# PMI_MotorDriver.net
KiCad netlist of a schematic drawn in Altium Designer
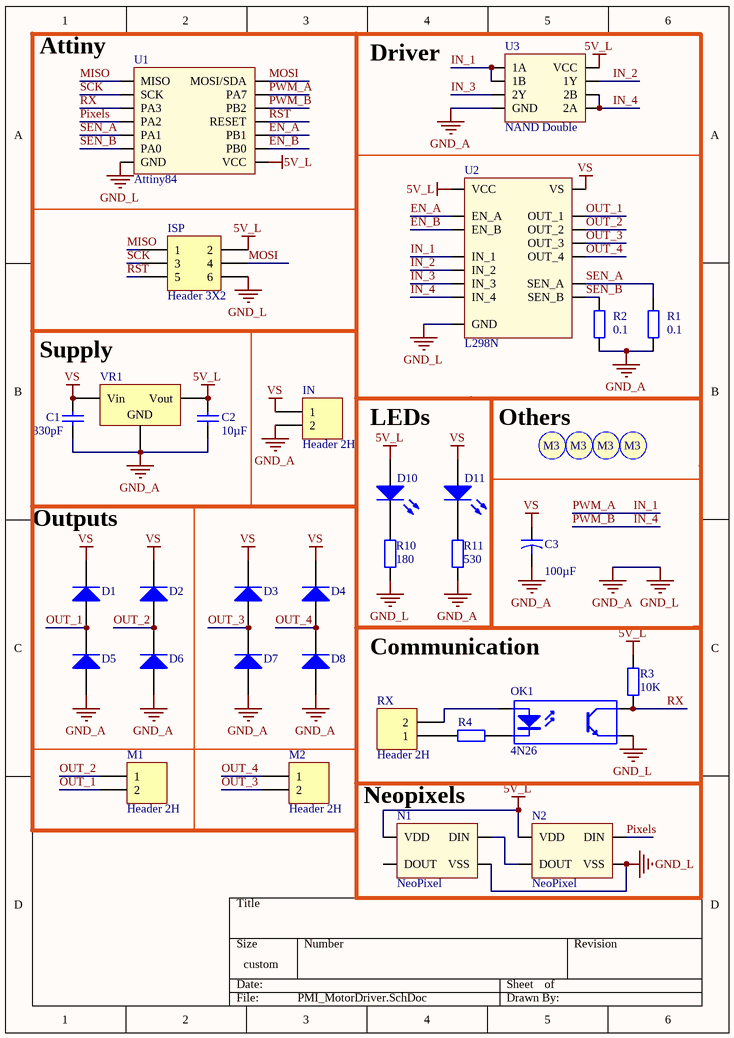
[diagram p0: PMI_MotorDriver.SchDoc]

(export (version "E")
  (design (tool "Eeschema 10.0.6"))
  (components
    (comp (ref "C1")
      (value "330pF")
      (footprint "3.2X1.6X1.1")
      (description "Capacitor")
      (fields (field (name "Comment") "Cap") (field (name "PUBLISHER") "Altium Limited"))
      (libsource (lib "Miscellaneous Devices") (part "Cap"))
    )
    (comp (ref "C2")
      (value "10µF")
      (footprint "3.2X1.6X1.1")
      (description "Capacitor")
      (fields (field (name "Comment") "Cap") (field (name "PUBLISHER") "Altium Limited"))
      (libsource (lib "Miscellaneous Devices") (part "Cap"))
    )
    (comp (ref "C3")
      (value "100µF")
      (footprint "Condensateur")
      (description "Capacitor")
      (fields (field (name "Comment") "Cap2") (field (name "PUBLISHER") "Altium Limited"))
      (libsource (lib "Miscellaneous Devices") (part "Cap2"))
    )
    (comp (ref "D1")
      (value "GF1G-E3/5CA (710-2976)")
      (footprint "DO-214BA")
      (description "Default Diode")
      (fields (field (name "PUBLISHER") "Altium Limited"))
      (libsource (lib "Miscellaneous Devices") (part "Diode"))
    )
    (comp (ref "D2")
      (value "Diode")
      (footprint "DO-214BA")
      (description "Default Diode")
      (fields (field (name "PUBLISHER") "Altium Limited"))
      (libsource (lib "Miscellaneous Devices") (part "Diode"))
    )
    (comp (ref "D3")
      (value "Diode")
      (footprint "DO-214BA")
      (description "Default Diode")
      (fields (field (name "PUBLISHER") "Altium Limited"))
      (libsource (lib "Miscellaneous Devices") (part "Diode"))
    )
    (comp (ref "D4")
      (value "Diode")
      (footprint "DO-214BA")
      (description "Default Diode")
      (fields (field (name "PUBLISHER") "Altium Limited"))
      (libsource (lib "Miscellaneous Devices") (part "Diode"))
    )
    (comp (ref "D5")
      (value "Diode")
      (footprint "DO-214BA")
      (description "Default Diode")
      (fields (field (name "PUBLISHER") "Altium Limited"))
      (libsource (lib "Miscellaneous Devices") (part "Diode"))
    )
    (comp (ref "D6")
      (value "Diode")
      (footprint "DO-214BA")
      (description "Default Diode")
      (fields (field (name "PUBLISHER") "Altium Limited"))
      (libsource (lib "Miscellaneous Devices") (part "Diode"))
    )
    (comp (ref "D7")
      (value "Diode")
      (footprint "DO-214BA")
      (description "Default Diode")
      (fields (field (name "PUBLISHER") "Altium Limited"))
      (libsource (lib "Miscellaneous Devices") (part "Diode"))
    )
    (comp (ref "D8")
      (value "Diode")
      (footprint "DO-214BA")
      (description "Default Diode")
      (fields (field (name "PUBLISHER") "Altium Limited"))
      (libsource (lib "Miscellaneous Devices") (part "Diode"))
    )
    (comp (ref "D10")
      (value "LED2")
      (footprint "3.2X1.6X1.1")
      (description "Typical RED, GREEN, YELLOW, AMBER GaAs LED")
      (fields (field (name "PUBLISHER") "Altium Limited"))
      (libsource (lib "Miscellaneous Devices") (part "LED2"))
    )
    (comp (ref "D11")
      (value "LED2")
      (footprint "3.2X1.6X1.1")
      (description "Typical RED, GREEN, YELLOW, AMBER GaAs LED")
      (fields (field (name "PUBLISHER") "Altium Limited"))
      (libsource (lib "Miscellaneous Devices") (part "LED2"))
    )
    (comp (ref "IN")
      (value "Header 2H")
      (footprint "Molex SPOX 2x1H")
      (description "Header, 2-Pin, Right Angle")
      (fields (field (name "PUBLISHER") "Altium Limited"))
      (libsource (lib "") (part "Header 2H_1"))
    )
    (comp (ref "ISP")
      (value "Header 3X2")
      (footprint "HDR2X3")
      (description "Header, 3-Pin, Dual row")
      (fields (field (name "PUBLISHER") "Altium Limited"))
      (libsource (lib "Miscellaneous Connectors") (part "Header 3X2"))
    )
    (comp (ref "M1")
      (value "Header 2H")
      (footprint "Molex SPOX 2x1H")
      (description "Header, 2-Pin, Right Angle")
      (fields (field (name "PUBLISHER") "Altium Limited"))
      (libsource (lib "") (part "Header 2H_1"))
    )
    (comp (ref "M2")
      (value "Header 2H")
      (footprint "Molex SPOX 2x1H")
      (description "Header, 2-Pin, Right Angle")
      (fields (field (name "PUBLISHER") "Altium Limited"))
      (libsource (lib "") (part "Header 2H_1"))
    )
    (comp (ref "N1")
      (value "NeoPixel")
      (footprint "Robot_2019:Neopixel")
      (libsource (lib "Robot_2019") (part "NeoPixel"))
    )
    (comp (ref "N2")
      (value "NeoPixel")
      (footprint "Robot_2019:Neopixel")
      (libsource (lib "Robot_2019") (part "NeoPixel"))
    )
    (comp (ref "OK1")
      (value "4N26")
      (footprint "4N26")
      (description "4-Pin Phototransistor Optocoupler")
      (fields (field (name "PUBLISHER") "Altium Limited"))
      (libsource (lib "Miscellaneous Devices") (part "Optoisolator1"))
    )
    (comp (ref "R1")
      (value "0.1")
      (footprint "CRA2512")
      (description "Resistor")
      (fields (field (name "Comment") "Res2") (field (name "PUBLISHER") "Altium Limited"))
      (libsource (lib "") (part "Res2_2"))
    )
    (comp (ref "R2")
      (value "0.1")
      (footprint "CRA2512")
      (description "Resistor")
      (fields (field (name "Comment") "Res2") (field (name "PUBLISHER") "Altium Limited"))
      (libsource (lib "") (part "Res2_2"))
    )
    (comp (ref "R3")
      (value "10K")
      (footprint "3.2X1.6X1.1")
      (description "Resistor")
      (fields (field (name "Comment") "Res2") (field (name "PUBLISHER") "Altium Limited"))
      (libsource (lib "") (part "Res2_2"))
    )
    (comp (ref "R4")
      (value "Res2")
      (footprint "3.2X1.6X1.1")
      (description "Resistor")
      (fields (field (name "PUBLISHER") "Altium Limited"))
      (libsource (lib "") (part "Res2_1"))
    )
    (comp (ref "R10")
      (value "180")
      (footprint "3.2X1.6X1.1")
      (description "Resistor")
      (fields (field (name "Comment") "Res2") (field (name "PUBLISHER") "Altium Limited"))
      (libsource (lib "Miscellaneous Devices") (part "Res2"))
    )
    (comp (ref "R11")
      (value "530")
      (footprint "3.2X1.6X1.1")
      (description "Resistor")
      (fields (field (name "Comment") "Res2") (field (name "PUBLISHER") "Altium Limited"))
      (libsource (lib "Miscellaneous Devices") (part "Res2"))
    )
    (comp (ref "RX")
      (value "Header 2H")
      (footprint "Molex SPOX 2x1H")
      (description "Header, 2-Pin, Right Angle")
      (fields (field (name "PUBLISHER") "Altium Limited"))
      (libsource (lib "Miscellaneous Connectors") (part "Header 2H"))
    )
    (comp (ref "S1")
      (value "Screw M3")
      (footprint "Robot_2019:Screw M3")
      (libsource (lib "Robot_2019") (part "Screw M3"))
    )
    (comp (ref "S2")
      (value "Screw M3")
      (footprint "Robot_2019:Screw M3")
      (libsource (lib "Robot_2019") (part "Screw M3"))
    )
    (comp (ref "S3")
      (value "Screw M3")
      (footprint "Robot_2019:Screw M3")
      (libsource (lib "Robot_2019") (part "Screw M3"))
    )
    (comp (ref "S4")
      (value "Screw M3")
      (footprint "Robot_2019:Screw M3")
      (libsource (lib "Robot_2019") (part "Screw M3"))
    )
    (comp (ref "U1")
      (value "Attiny84")
      (footprint "Robot_2019:Attiny84 SOIC")
      (libsource (lib "Robot_2019") (part "Attiny84"))
    )
    (comp (ref "U2")
      (value "L298N")
      (footprint "L298N")
      (description "Motor Driver 2 outputs")
      (libsource (lib "Robot_2019") (part "L298N"))
    )
    (comp (ref "U3")
      (value "NAND Double")
      (footprint "SOIC_8")
      (libsource (lib "Robot_2019") (part "NAND Double"))
    )
    (comp (ref "VR1")
      (value "BA178M05FP-E2")
      (footprint "TO-252")
      (description "Voltage Regulator")
      (fields (field (name "PUBLISHER") "Altium Limited"))
      (libsource (lib "Miscellaneous Devices") (part "Volt Reg"))
    )
  )
  (nets
    (net (code "1") (name "/EN_A") (class "Default")
      (node (ref "U1") (pin "3") (pinfunction "PB1_3") (pintype "passive"))
      (node (ref "U2") (pin "6") (pinfunction "EN_A_6") (pintype "passive"))
    )
    (net (code "2") (name "/EN_B") (class "Default")
      (node (ref "U1") (pin "2") (pinfunction "PB0_2") (pintype "passive"))
      (node (ref "U2") (pin "11") (pinfunction "EN_B_11") (pintype "passive"))
    )
    (net (code "3") (name "/IN_1") (class "Default")
      (node (ref "U1") (pin "6") (pinfunction "PA7_6") (pintype "passive"))
      (node (ref "U2") (pin "5") (pinfunction "IN_1_5") (pintype "passive"))
      (node (ref "U3") (pin "1") (pinfunction "1A_1") (pintype "passive"))
      (node (ref "U3") (pin "2") (pinfunction "1B_2") (pintype "passive"))
    )
    (net (code "4") (name "/IN_2") (class "Default")
      (node (ref "U2") (pin "7") (pinfunction "IN_2_7") (pintype "passive"))
      (node (ref "U3") (pin "7") (pinfunction "1Y_7") (pintype "passive"))
    )
    (net (code "5") (name "/IN_3") (class "Default")
      (node (ref "U2") (pin "10") (pinfunction "IN_3_10") (pintype "passive"))
      (node (ref "U3") (pin "3") (pinfunction "2Y_3") (pintype "passive"))
    )
    (net (code "6") (name "/IN_4") (class "Default")
      (node (ref "U1") (pin "5") (pinfunction "PB2_5") (pintype "passive"))
      (node (ref "U2") (pin "12") (pinfunction "IN_4_12") (pintype "passive"))
      (node (ref "U3") (pin "5") (pinfunction "2A_5") (pintype "passive"))
      (node (ref "U3") (pin "6") (pinfunction "2B_6") (pintype "passive"))
    )
    (net (code "7") (name "/MISO") (class "Default")
      (node (ref "ISP") (pin "1") (pinfunction "1_1") (pintype "passive"))
      (node (ref "U1") (pin "8") (pinfunction "MISO_8") (pintype "passive"))
    )
    (net (code "8") (name "/MOSI") (class "Default")
      (node (ref "ISP") (pin "4") (pinfunction "4_4") (pintype "passive"))
      (node (ref "U1") (pin "7") (pinfunction "MOSI/SDA_7") (pintype "passive"))
    )
    (net (code "9") (name "/OUT_1") (class "Default")
      (node (ref "D1") (pin "1") (pinfunction "A_1") (pintype "passive"))
      (node (ref "D5") (pin "2") (pinfunction "K_2") (pintype "passive"))
      (node (ref "M1") (pin "2") (pinfunction "2_2") (pintype "passive"))
      (node (ref "U2") (pin "2") (pinfunction "OUT_1_2") (pintype "passive"))
    )
    (net (code "10") (name "/OUT_2") (class "Default")
      (node (ref "D2") (pin "1") (pinfunction "A_1") (pintype "passive"))
      (node (ref "D6") (pin "2") (pinfunction "K_2") (pintype "passive"))
      (node (ref "M1") (pin "1") (pinfunction "1_1") (pintype "passive"))
      (node (ref "U2") (pin "3") (pinfunction "OUT_2_3") (pintype "passive"))
    )
    (net (code "11") (name "/OUT_3") (class "Default")
      (node (ref "D3") (pin "1") (pinfunction "A_1") (pintype "passive"))
      (node (ref "D7") (pin "2") (pinfunction "K_2") (pintype "passive"))
      (node (ref "M2") (pin "2") (pinfunction "2_2") (pintype "passive"))
      (node (ref "U2") (pin "13") (pinfunction "OUT_3_13") (pintype "passive"))
    )
    (net (code "12") (name "/OUT_4") (class "Default")
      (node (ref "D4") (pin "1") (pinfunction "A_1") (pintype "passive"))
      (node (ref "D8") (pin "2") (pinfunction "K_2") (pintype "passive"))
      (node (ref "M2") (pin "1") (pinfunction "1_1") (pintype "passive"))
      (node (ref "U2") (pin "14") (pinfunction "OUT_4_14") (pintype "passive"))
    )
    (net (code "13") (name "/Pixels") (class "Default")
      (node (ref "N2") (pin "3") (pinfunction "DIN_3") (pintype "passive"))
      (node (ref "U1") (pin "11") (pinfunction "PA2_11") (pintype "passive"))
    )
    (net (code "14") (name "/RST") (class "Default")
      (node (ref "ISP") (pin "5") (pinfunction "5_5") (pintype "passive"))
      (node (ref "U1") (pin "4") (pinfunction "RESET_4") (pintype "passive"))
    )
    (net (code "15") (name "/RX") (class "Default")
      (node (ref "OK1") (pin "4") (pinfunction "C_4") (pintype "passive"))
      (node (ref "R3") (pin "1") (pinfunction "1_1") (pintype "passive"))
      (node (ref "U1") (pin "10") (pinfunction "PA3_10") (pintype "passive"))
    )
    (net (code "16") (name "/SCK") (class "Default")
      (node (ref "ISP") (pin "3") (pinfunction "3_3") (pintype "passive"))
      (node (ref "U1") (pin "9") (pinfunction "SCK_9") (pintype "passive"))
    )
    (net (code "17") (name "/SEN_A") (class "Default")
      (node (ref "R1") (pin "2") (pinfunction "2_2") (pintype "passive"))
      (node (ref "U1") (pin "12") (pinfunction "PA1_12") (pintype "passive"))
      (node (ref "U2") (pin "1") (pinfunction "SEN_A_1") (pintype "passive"))
    )
    (net (code "18") (name "/SEN_B") (class "Default")
      (node (ref "R2") (pin "2") (pinfunction "2_2") (pintype "passive"))
      (node (ref "U1") (pin "13") (pinfunction "PA0_13") (pintype "passive"))
      (node (ref "U2") (pin "15") (pinfunction "SEN_B_15") (pintype "passive"))
    )
    (net (code "19") (name "5V_L") (class "Default")
      (node (ref "C2") (pin "2") (pinfunction "2_2") (pintype "passive"))
      (node (ref "D10") (pin "1") (pinfunction "A_1") (pintype "passive"))
      (node (ref "ISP") (pin "2") (pinfunction "2_2") (pintype "passive"))
      (node (ref "N1") (pin "4") (pinfunction "VDD_4") (pintype "passive"))
      (node (ref "N2") (pin "4") (pinfunction "VDD_4") (pintype "passive"))
      (node (ref "R3") (pin "2") (pinfunction "2_2") (pintype "passive"))
      (node (ref "U1") (pin "1") (pinfunction "VCC_1") (pintype "passive"))
      (node (ref "U2") (pin "9") (pinfunction "VCC_9") (pintype "passive"))
      (node (ref "U3") (pin "8") (pinfunction "VCC_8") (pintype "passive"))
      (node (ref "VR1") (pin "3") (pinfunction "Vout_3") (pintype "passive"))
    )
    (net (code "20") (name "GND_A") (class "Default")
      (node (ref "C1") (pin "1") (pinfunction "1_1") (pintype "passive"))
      (node (ref "C2") (pin "1") (pinfunction "1_1") (pintype "passive"))
      (node (ref "C3") (pin "2") (pinfunction "2_2") (pintype "passive"))
      (node (ref "D5") (pin "1") (pinfunction "A_1") (pintype "passive"))
      (node (ref "D6") (pin "1") (pinfunction "A_1") (pintype "passive"))
      (node (ref "D7") (pin "1") (pinfunction "A_1") (pintype "passive"))
      (node (ref "D8") (pin "1") (pinfunction "A_1") (pintype "passive"))
      (node (ref "IN") (pin "2") (pinfunction "2_2") (pintype "passive"))
      (node (ref "ISP") (pin "6") (pinfunction "6_6") (pintype "passive"))
      (node (ref "N1") (pin "2") (pinfunction "VSS_2") (pintype "passive"))
      (node (ref "N2") (pin "2") (pinfunction "VSS_2") (pintype "passive"))
      (node (ref "OK1") (pin "3") (pinfunction "E_3") (pintype "passive"))
      (node (ref "R1") (pin "1") (pinfunction "1_1") (pintype "passive"))
      (node (ref "R10") (pin "2") (pinfunction "2_2") (pintype "passive"))
      (node (ref "R11") (pin "2") (pinfunction "2_2") (pintype "passive"))
      (node (ref "R2") (pin "1") (pinfunction "1_1") (pintype "passive"))
      (node (ref "U1") (pin "14") (pinfunction "GND_14") (pintype "passive"))
      (node (ref "U2") (pin "8") (pinfunction "GND_8") (pintype "passive"))
      (node (ref "U3") (pin "4") (pinfunction "GND_4") (pintype "passive"))
      (node (ref "VR1") (pin "2") (pinfunction "GND_2") (pintype "passive"))
    )
    (net (code "21") (name "Net-(D10-K)") (class "Default")
      (node (ref "D10") (pin "2") (pinfunction "K_2") (pintype "passive"))
      (node (ref "R10") (pin "1") (pinfunction "1_1") (pintype "passive"))
    )
    (net (code "22") (name "Net-(D11-K)") (class "Default")
      (node (ref "D11") (pin "2") (pinfunction "K_2") (pintype "passive"))
      (node (ref "R11") (pin "1") (pinfunction "1_1") (pintype "passive"))
    )
    (net (code "23") (name "Net-(N1-DIN)") (class "Default")
      (node (ref "N1") (pin "3") (pinfunction "DIN_3") (pintype "passive"))
      (node (ref "N2") (pin "1") (pinfunction "DOUT_1") (pintype "passive"))
    )
    (net (code "24") (name "Net-(OK1-A)") (class "Default")
      (node (ref "OK1") (pin "1") (pinfunction "A_1") (pintype "passive"))
      (node (ref "RX") (pin "2") (pinfunction "2_2") (pintype "passive"))
    )
    (net (code "25") (name "Net-(OK1-K)") (class "Default")
      (node (ref "OK1") (pin "2") (pinfunction "K_2") (pintype "passive"))
      (node (ref "R4") (pin "2") (pinfunction "2_2") (pintype "passive"))
    )
    (net (code "26") (name "Net-(R4-Pad1)") (class "Default")
      (node (ref "R4") (pin "1") (pinfunction "1_1") (pintype "passive"))
      (node (ref "RX") (pin "1") (pinfunction "1_1") (pintype "passive"))
    )
    (net (code "27") (name "VS") (class "Default")
      (node (ref "C1") (pin "2") (pinfunction "2_2") (pintype "passive"))
      (node (ref "C3") (pin "1") (pinfunction "1_1") (pintype "passive"))
      (node (ref "D1") (pin "2") (pinfunction "K_2") (pintype "passive"))
      (node (ref "D11") (pin "1") (pinfunction "A_1") (pintype "passive"))
      (node (ref "D2") (pin "2") (pinfunction "K_2") (pintype "passive"))
      (node (ref "D3") (pin "2") (pinfunction "K_2") (pintype "passive"))
      (node (ref "D4") (pin "2") (pinfunction "K_2") (pintype "passive"))
      (node (ref "IN") (pin "1") (pinfunction "1_1") (pintype "passive"))
      (node (ref "U2") (pin "4") (pinfunction "VS_4") (pintype "passive"))
      (node (ref "VR1") (pin "1") (pinfunction "Vin_1") (pintype "passive"))
    )
    (net (code "28") (name "unconnected-(N1-DOUT-Pad1)") (class "Default")
      (node (ref "N1") (pin "1") (pinfunction "DOUT_1") (pintype "passive"))
    )
  )
)
